# module_state.net
KiCad netlist of a schematic drawn in EAGLE
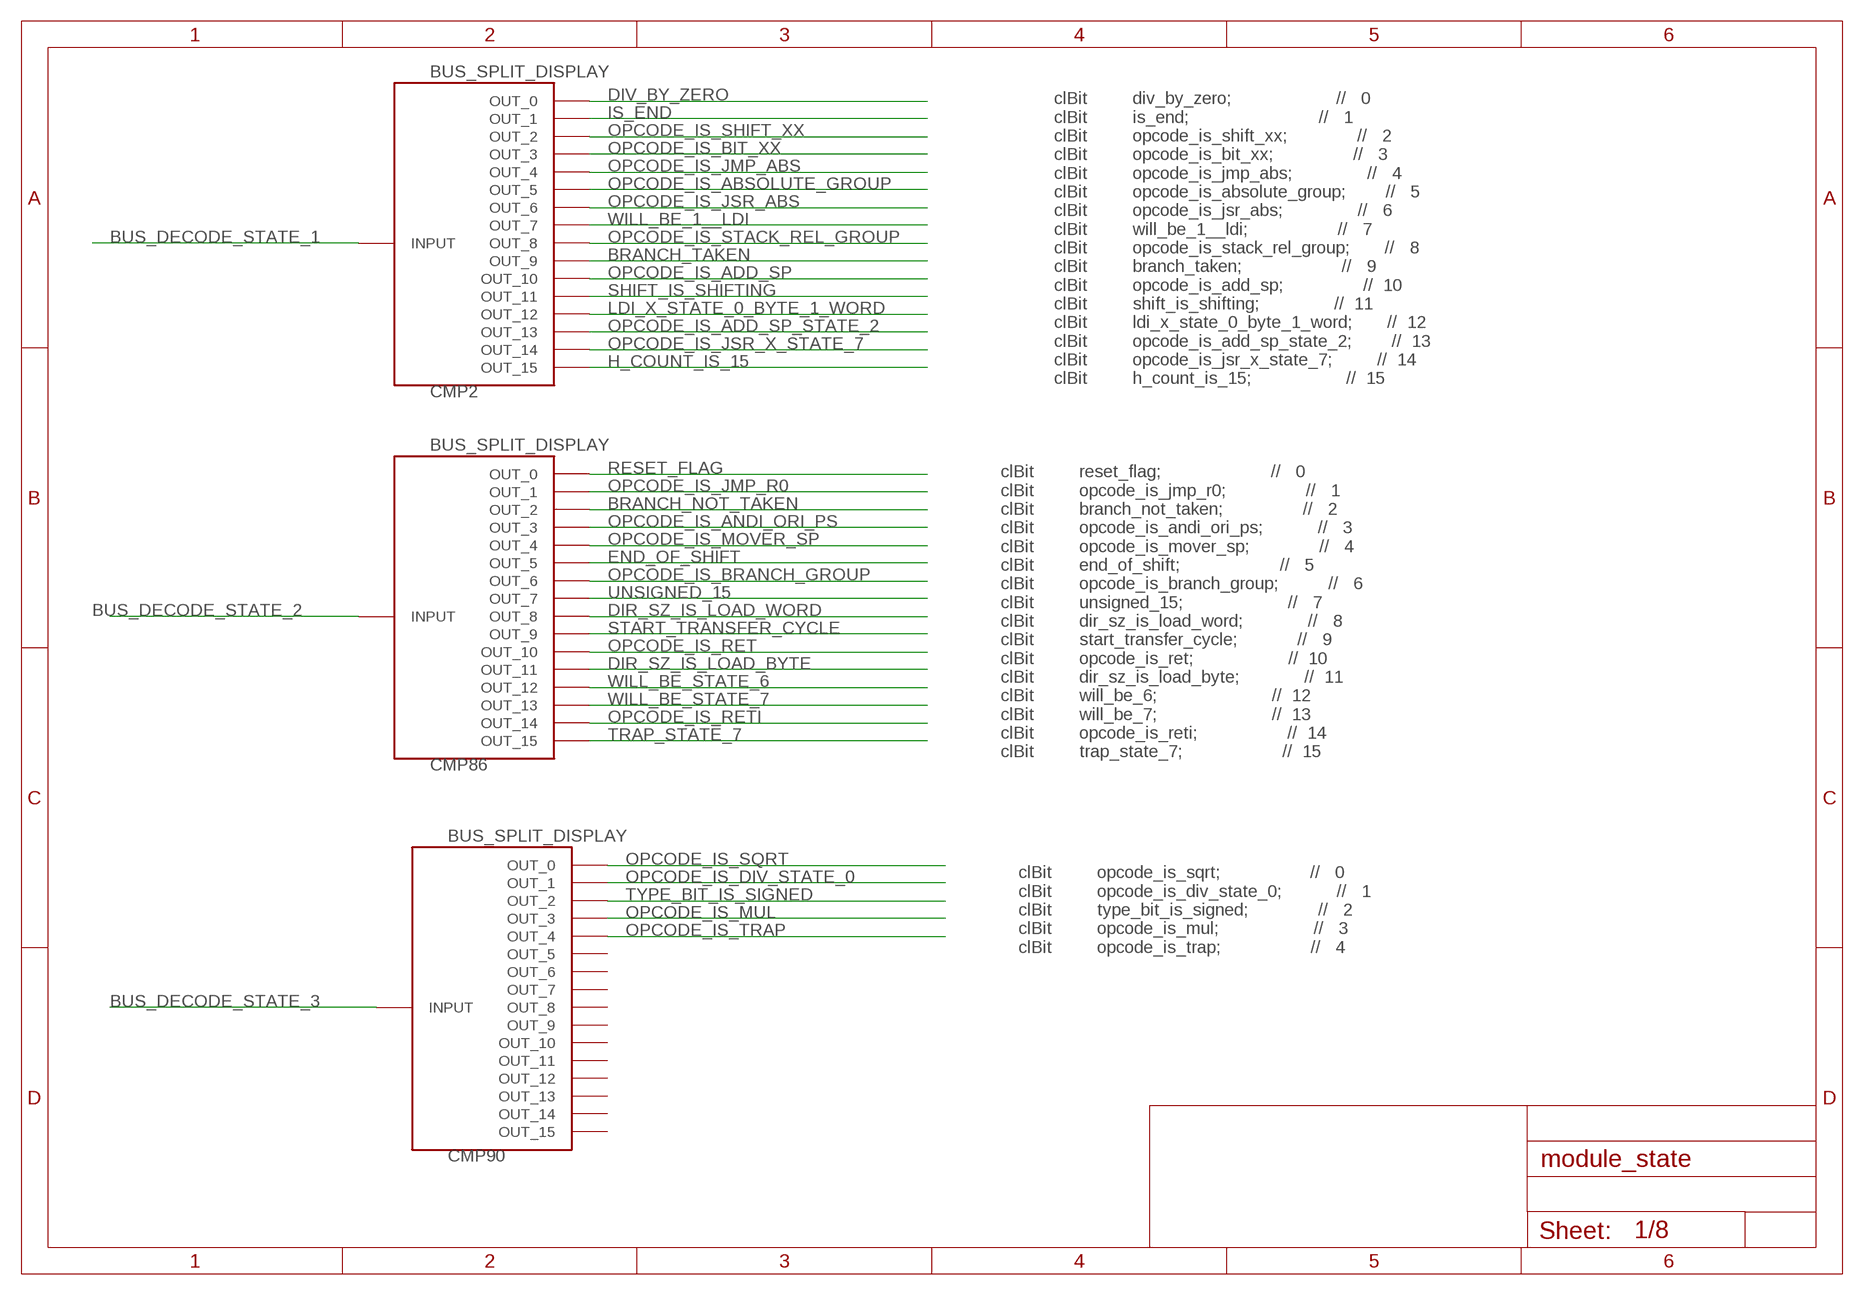
[diagram p0: schematic, sheet 1]
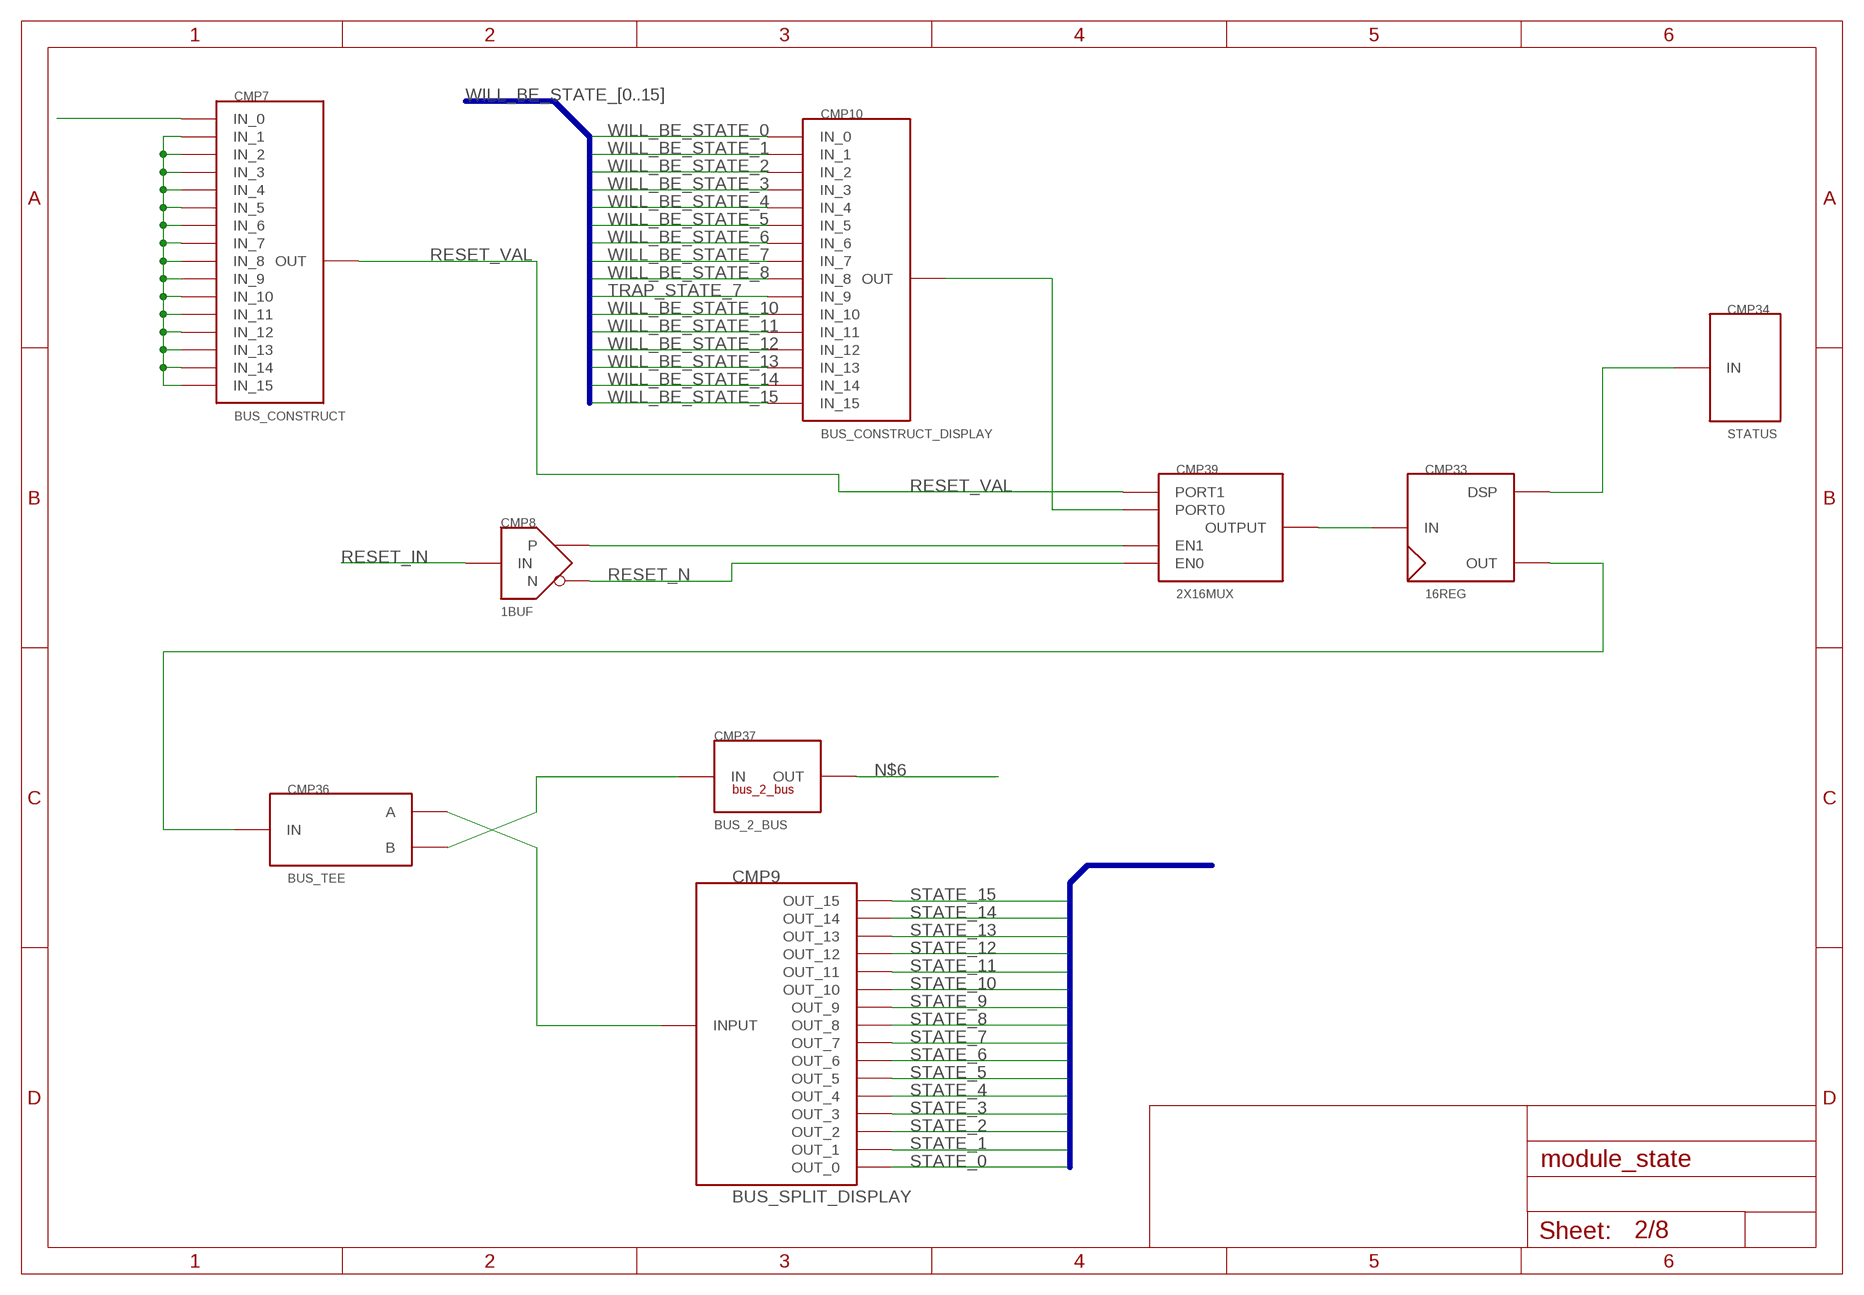
[diagram p1: schematic, sheet 2]
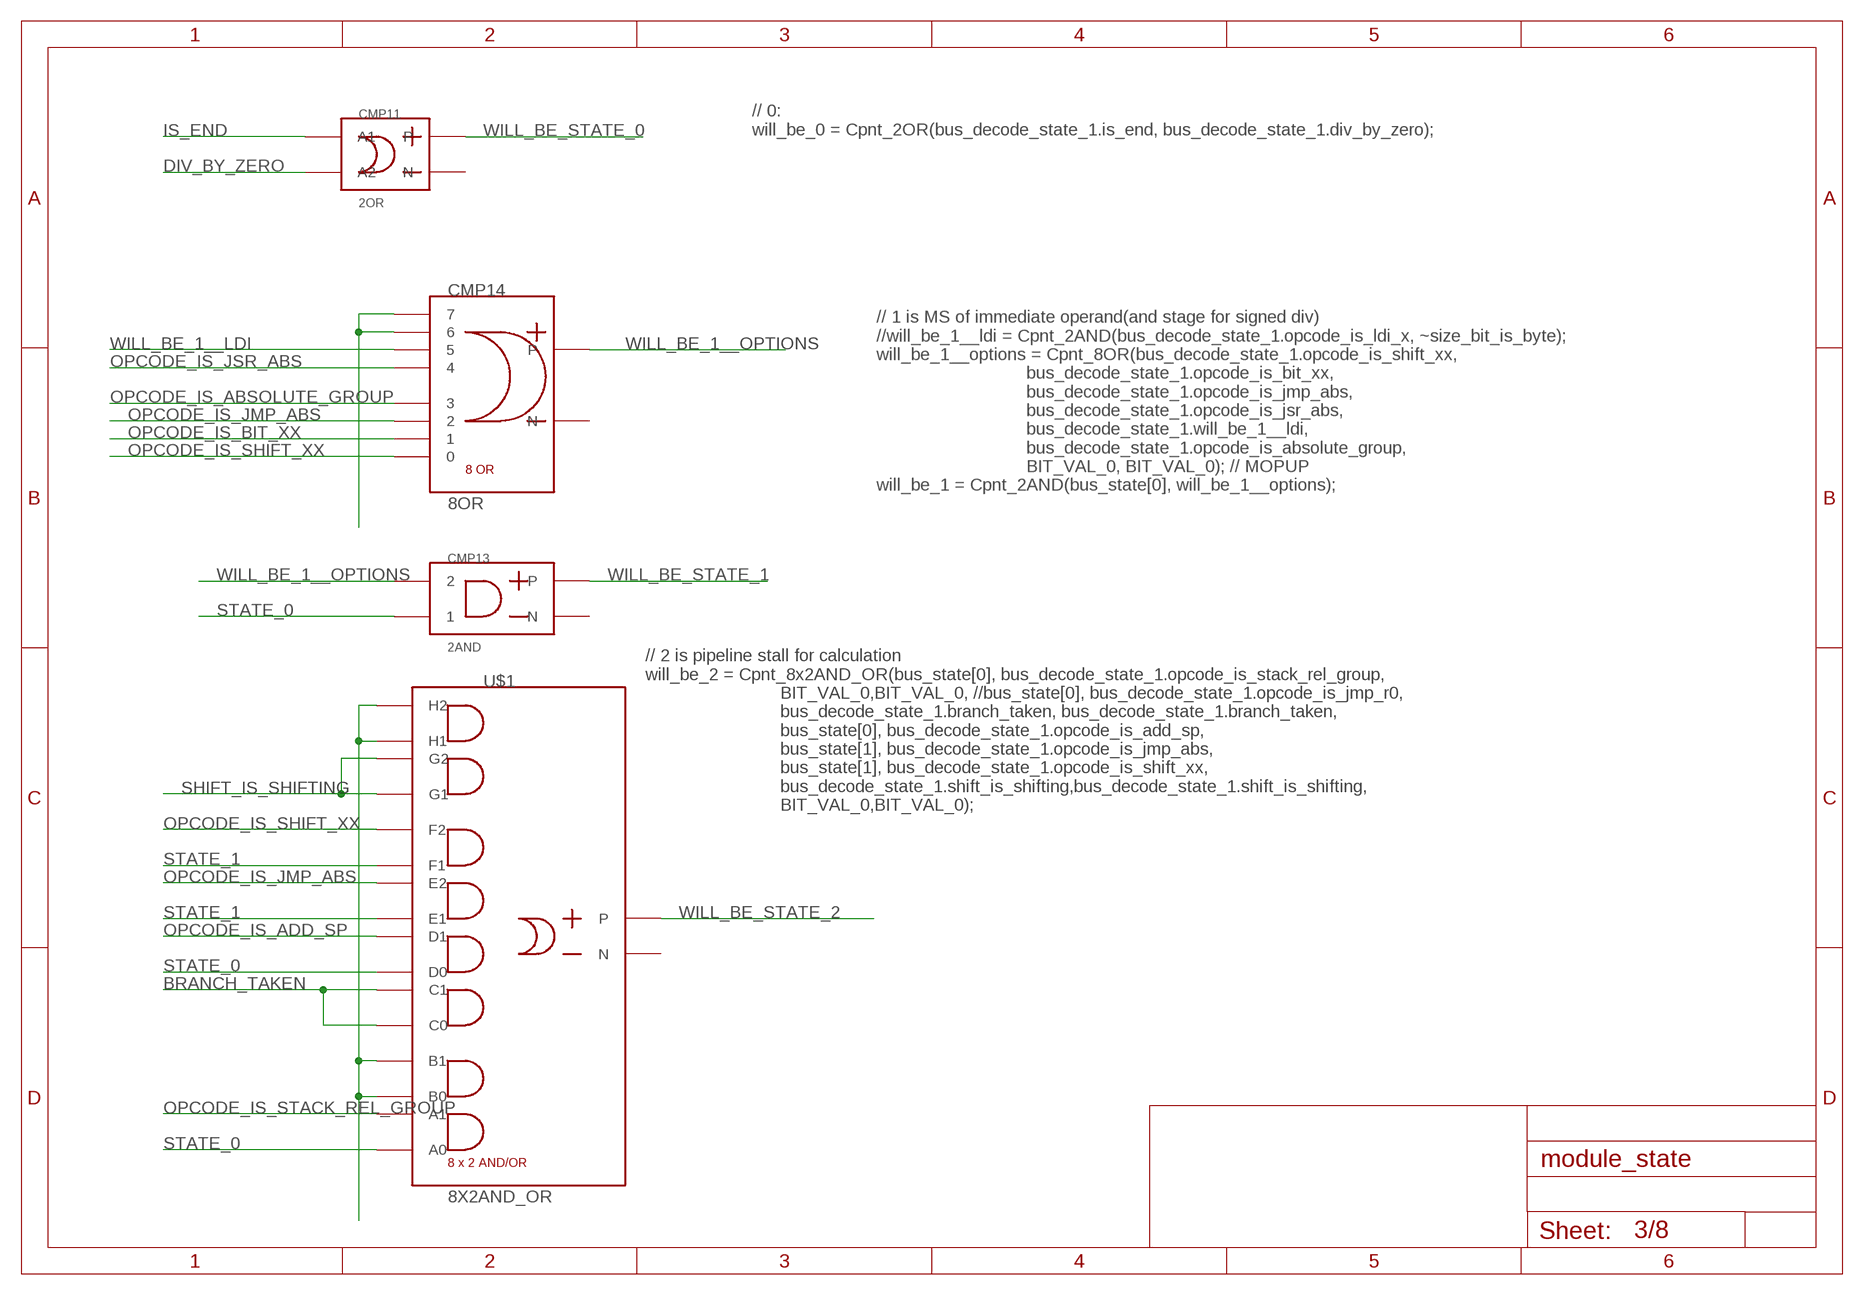
[diagram p2: schematic, sheet 3]
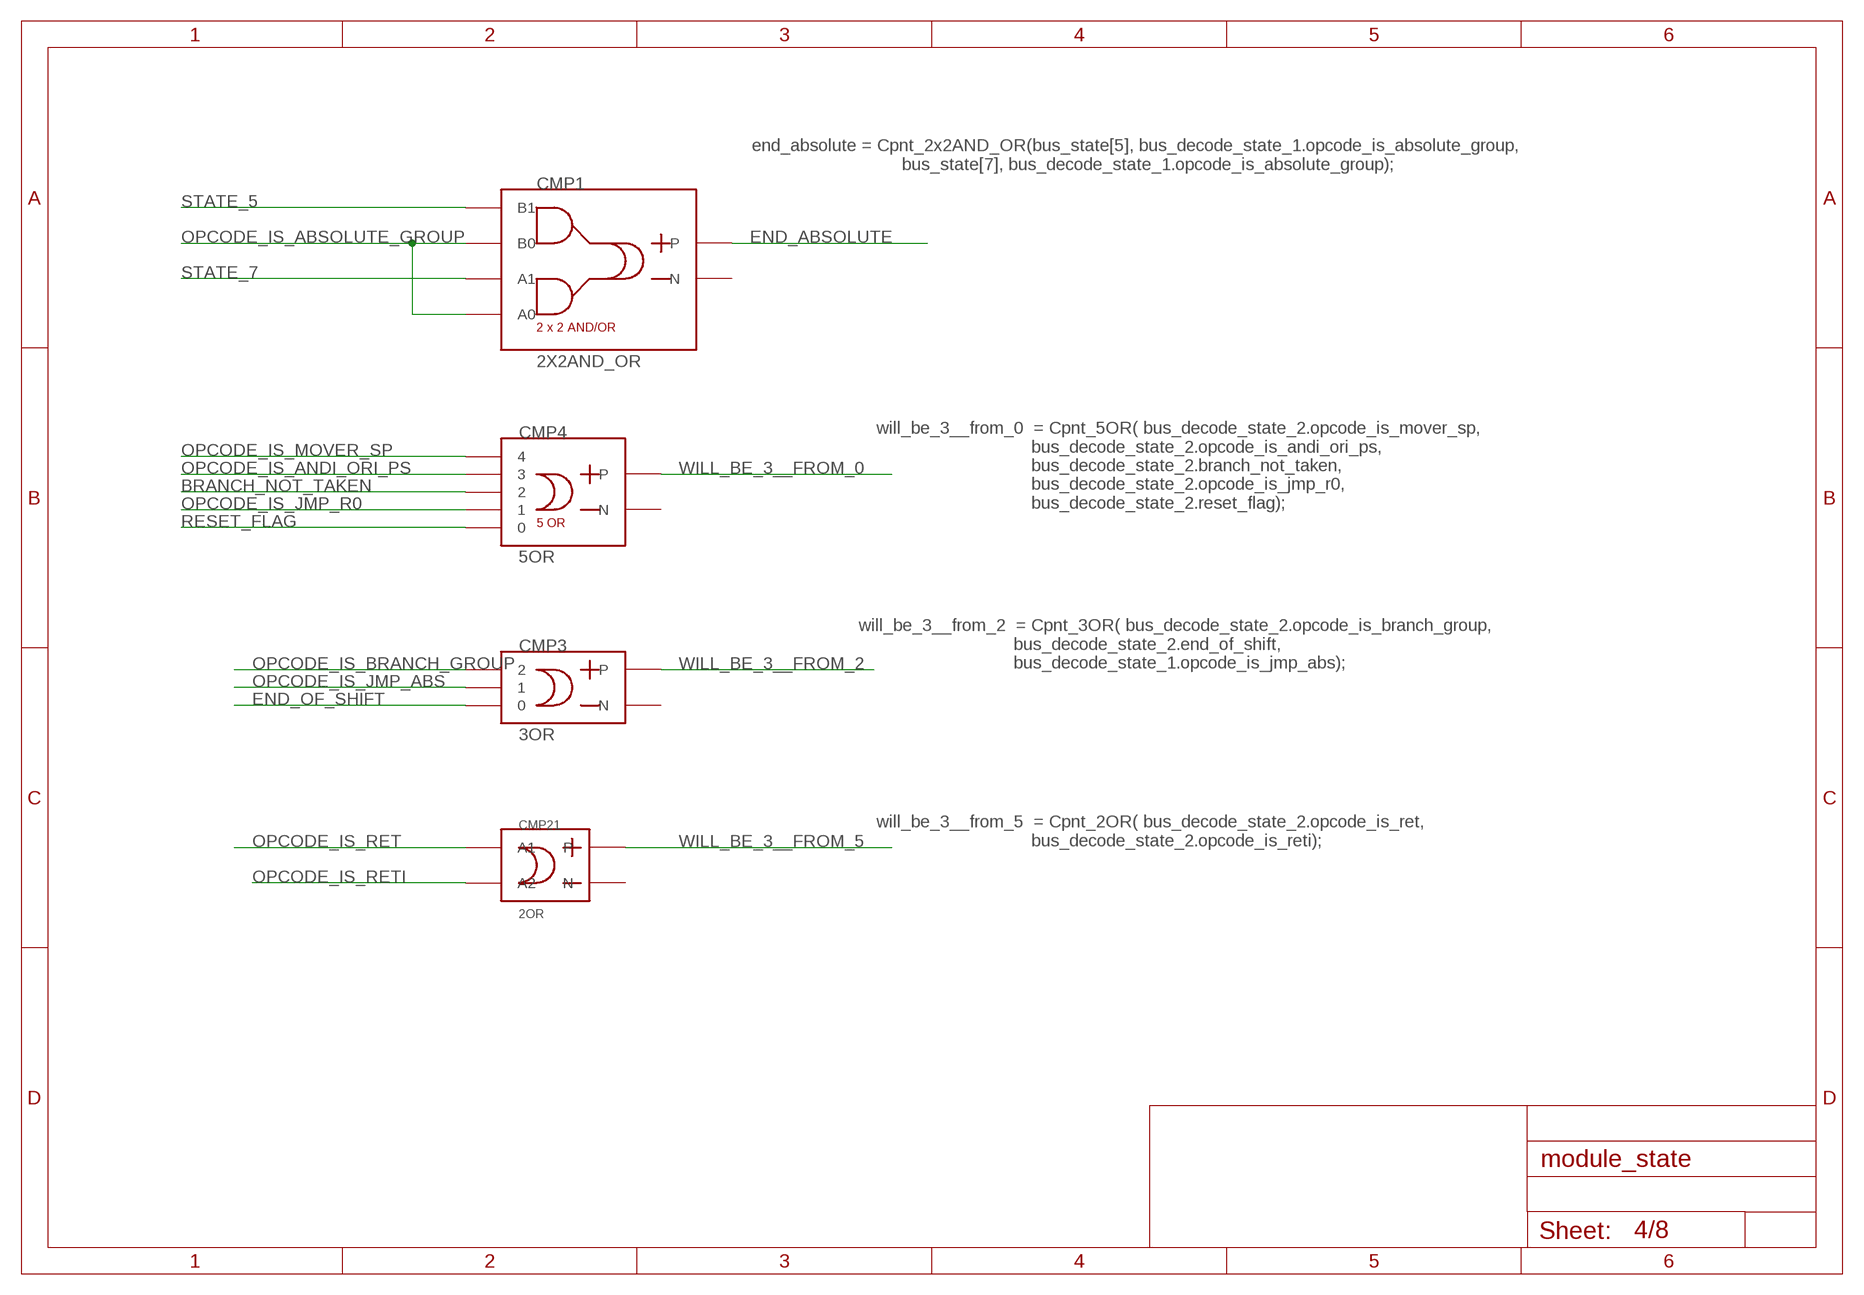
[diagram p3: schematic, sheet 4]
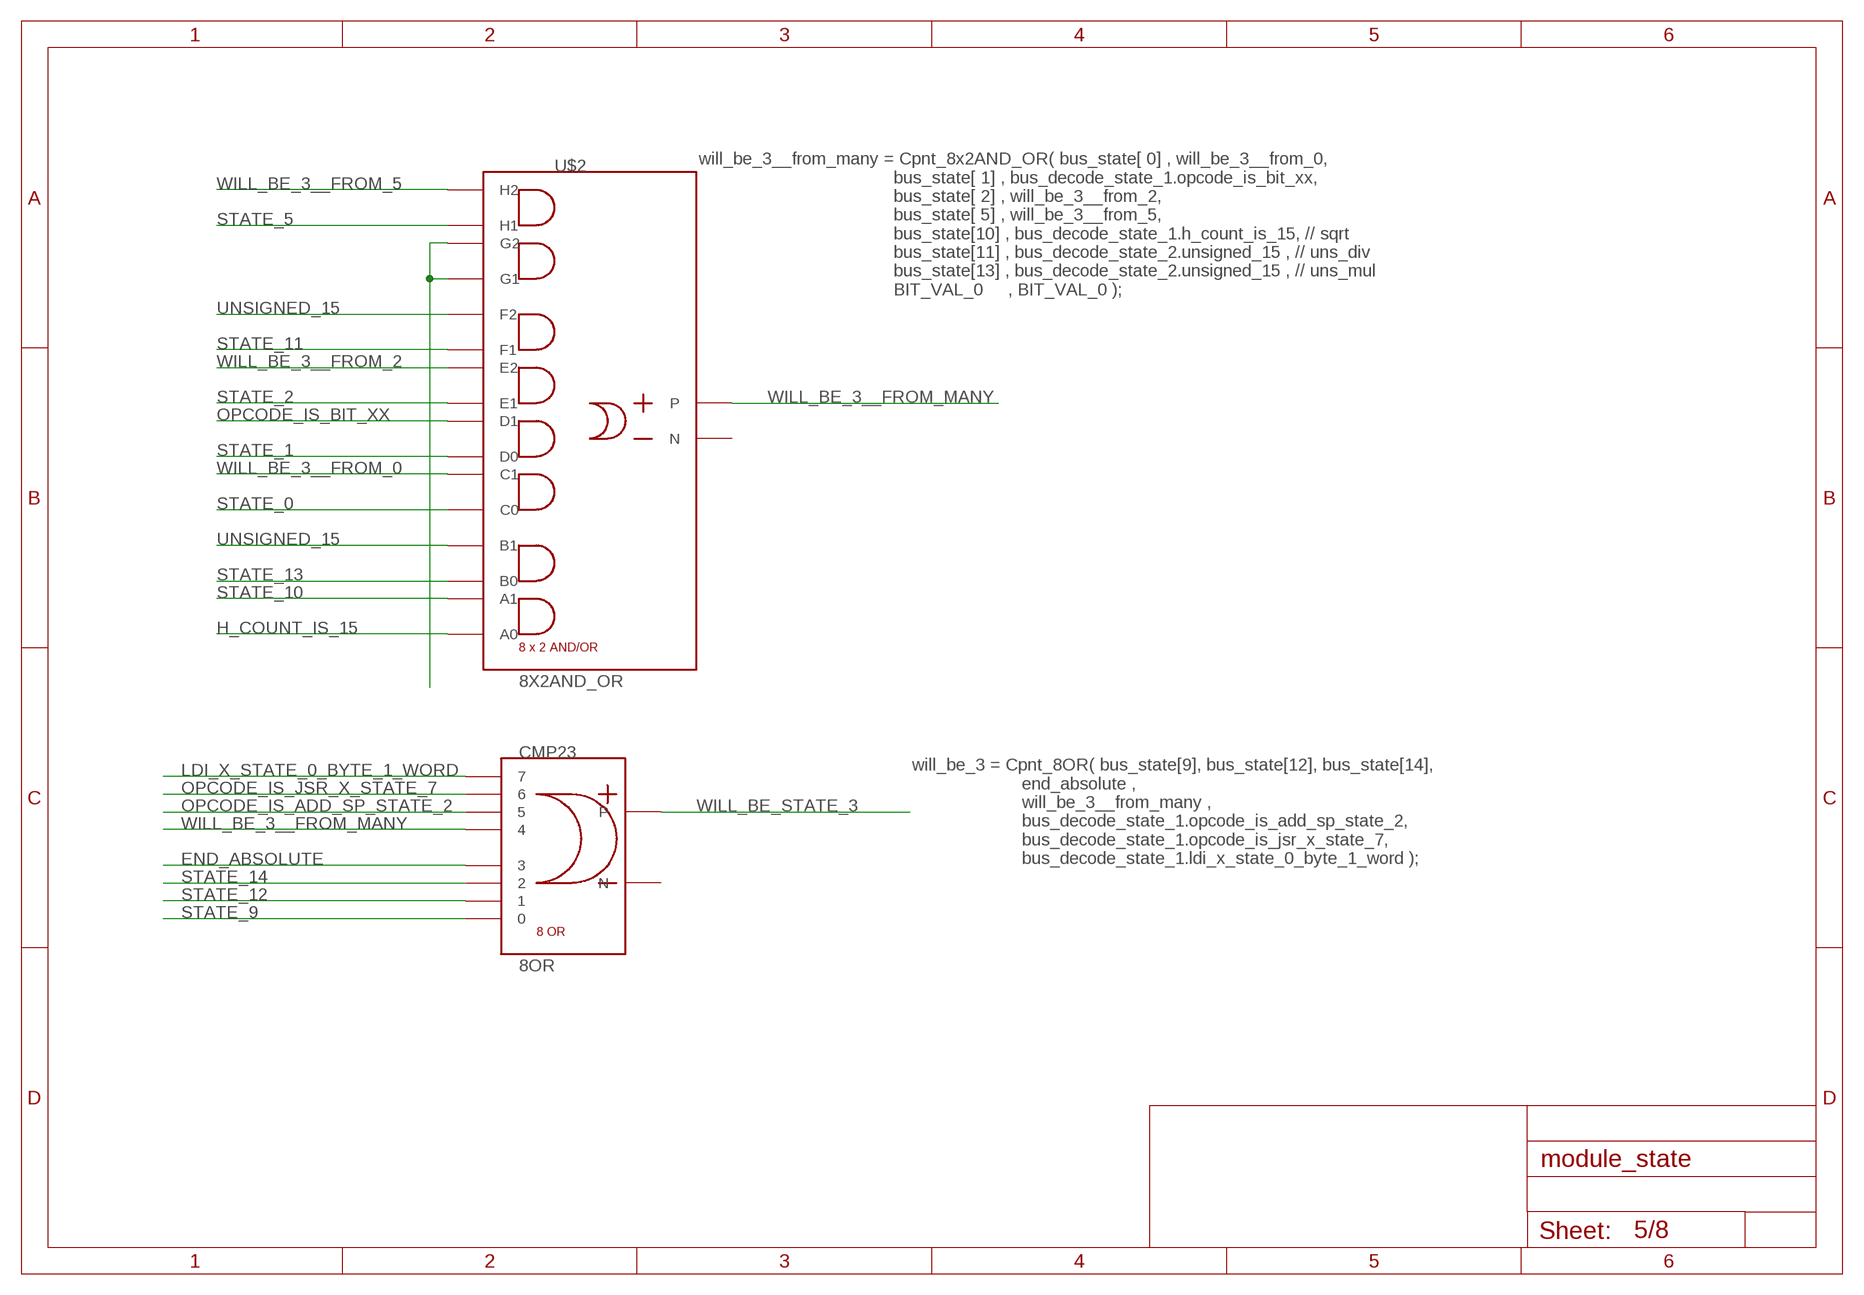
[diagram p4: schematic, sheet 5]
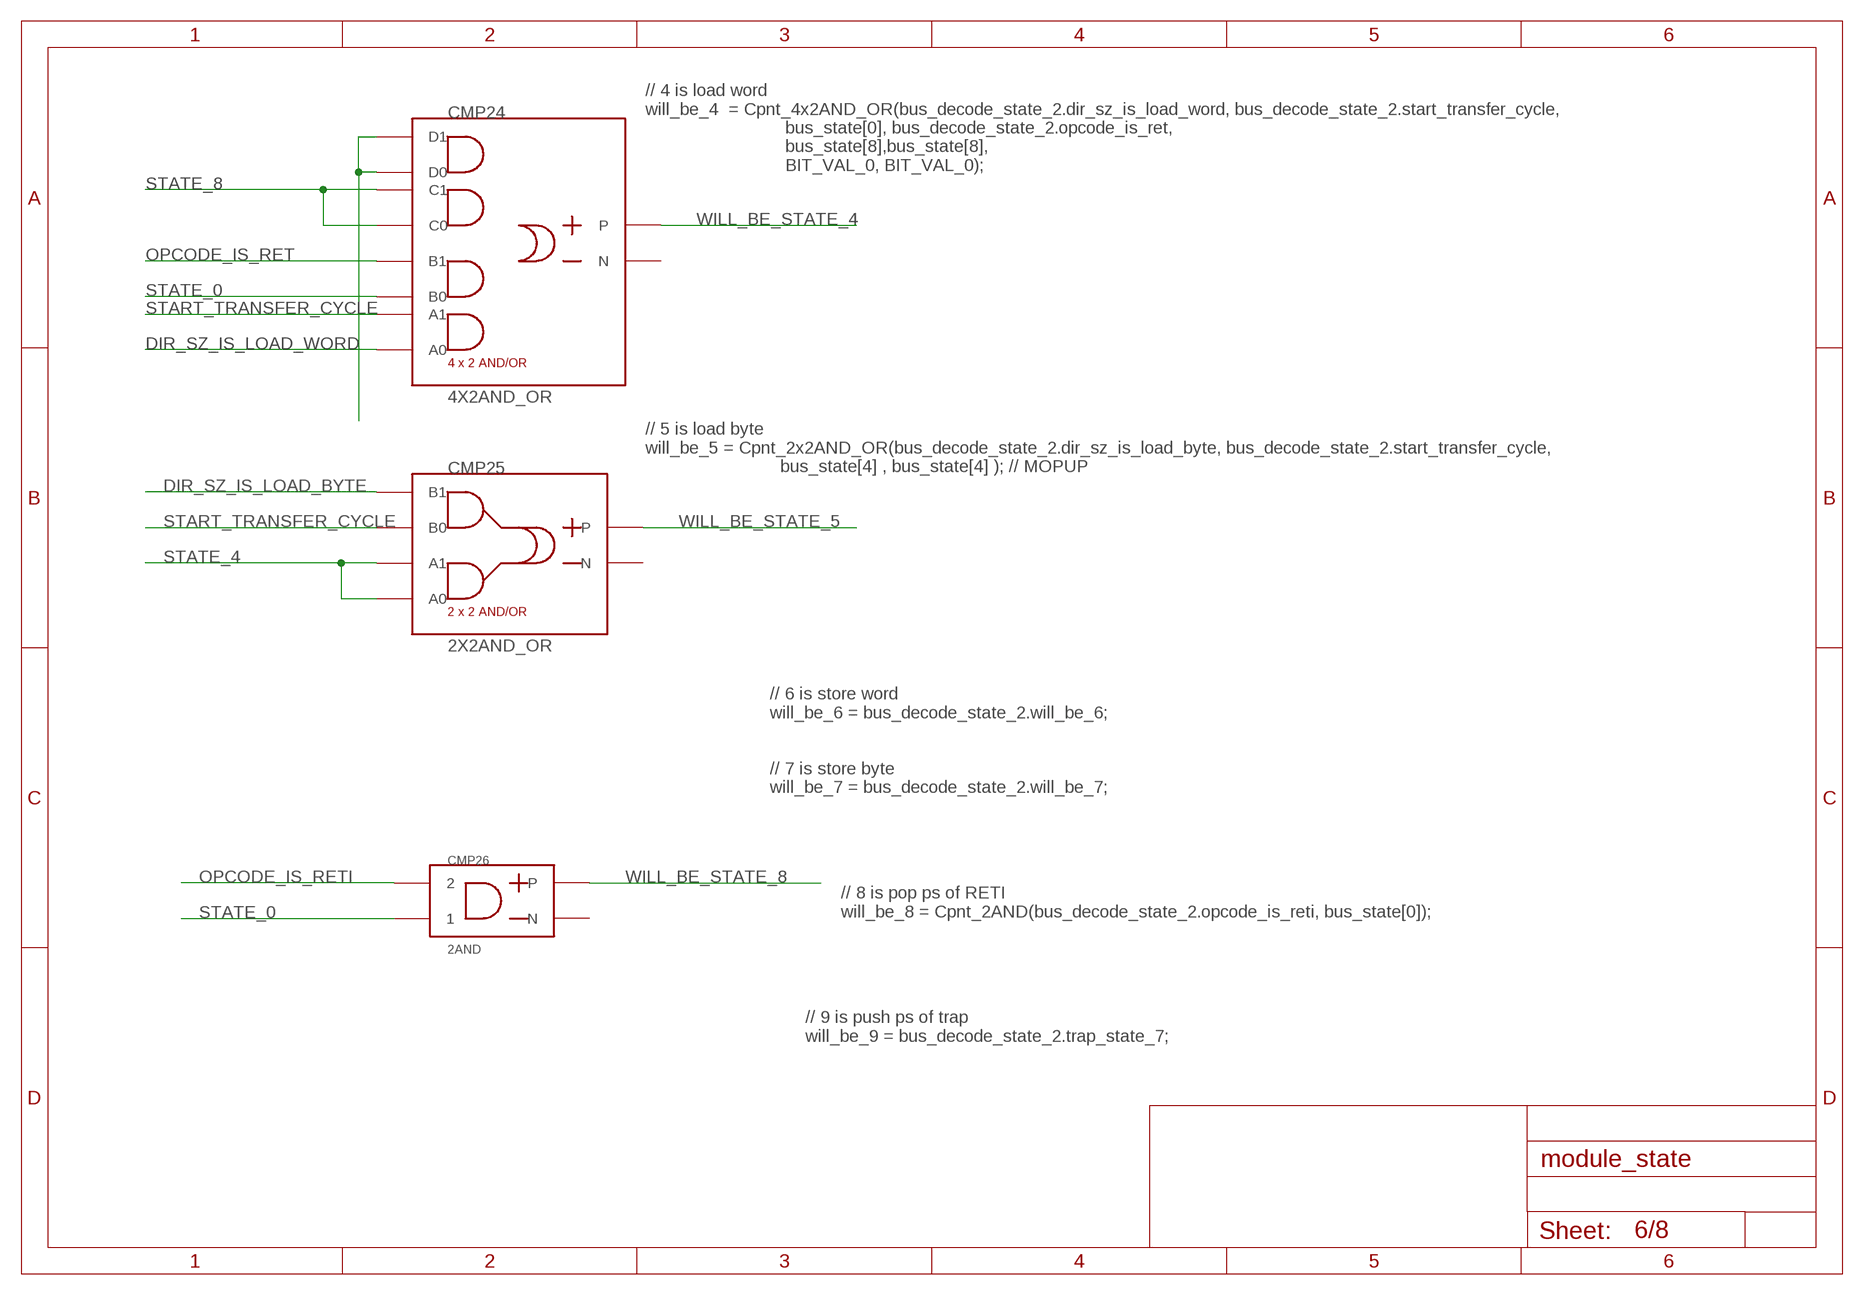
[diagram p5: schematic, sheet 6]
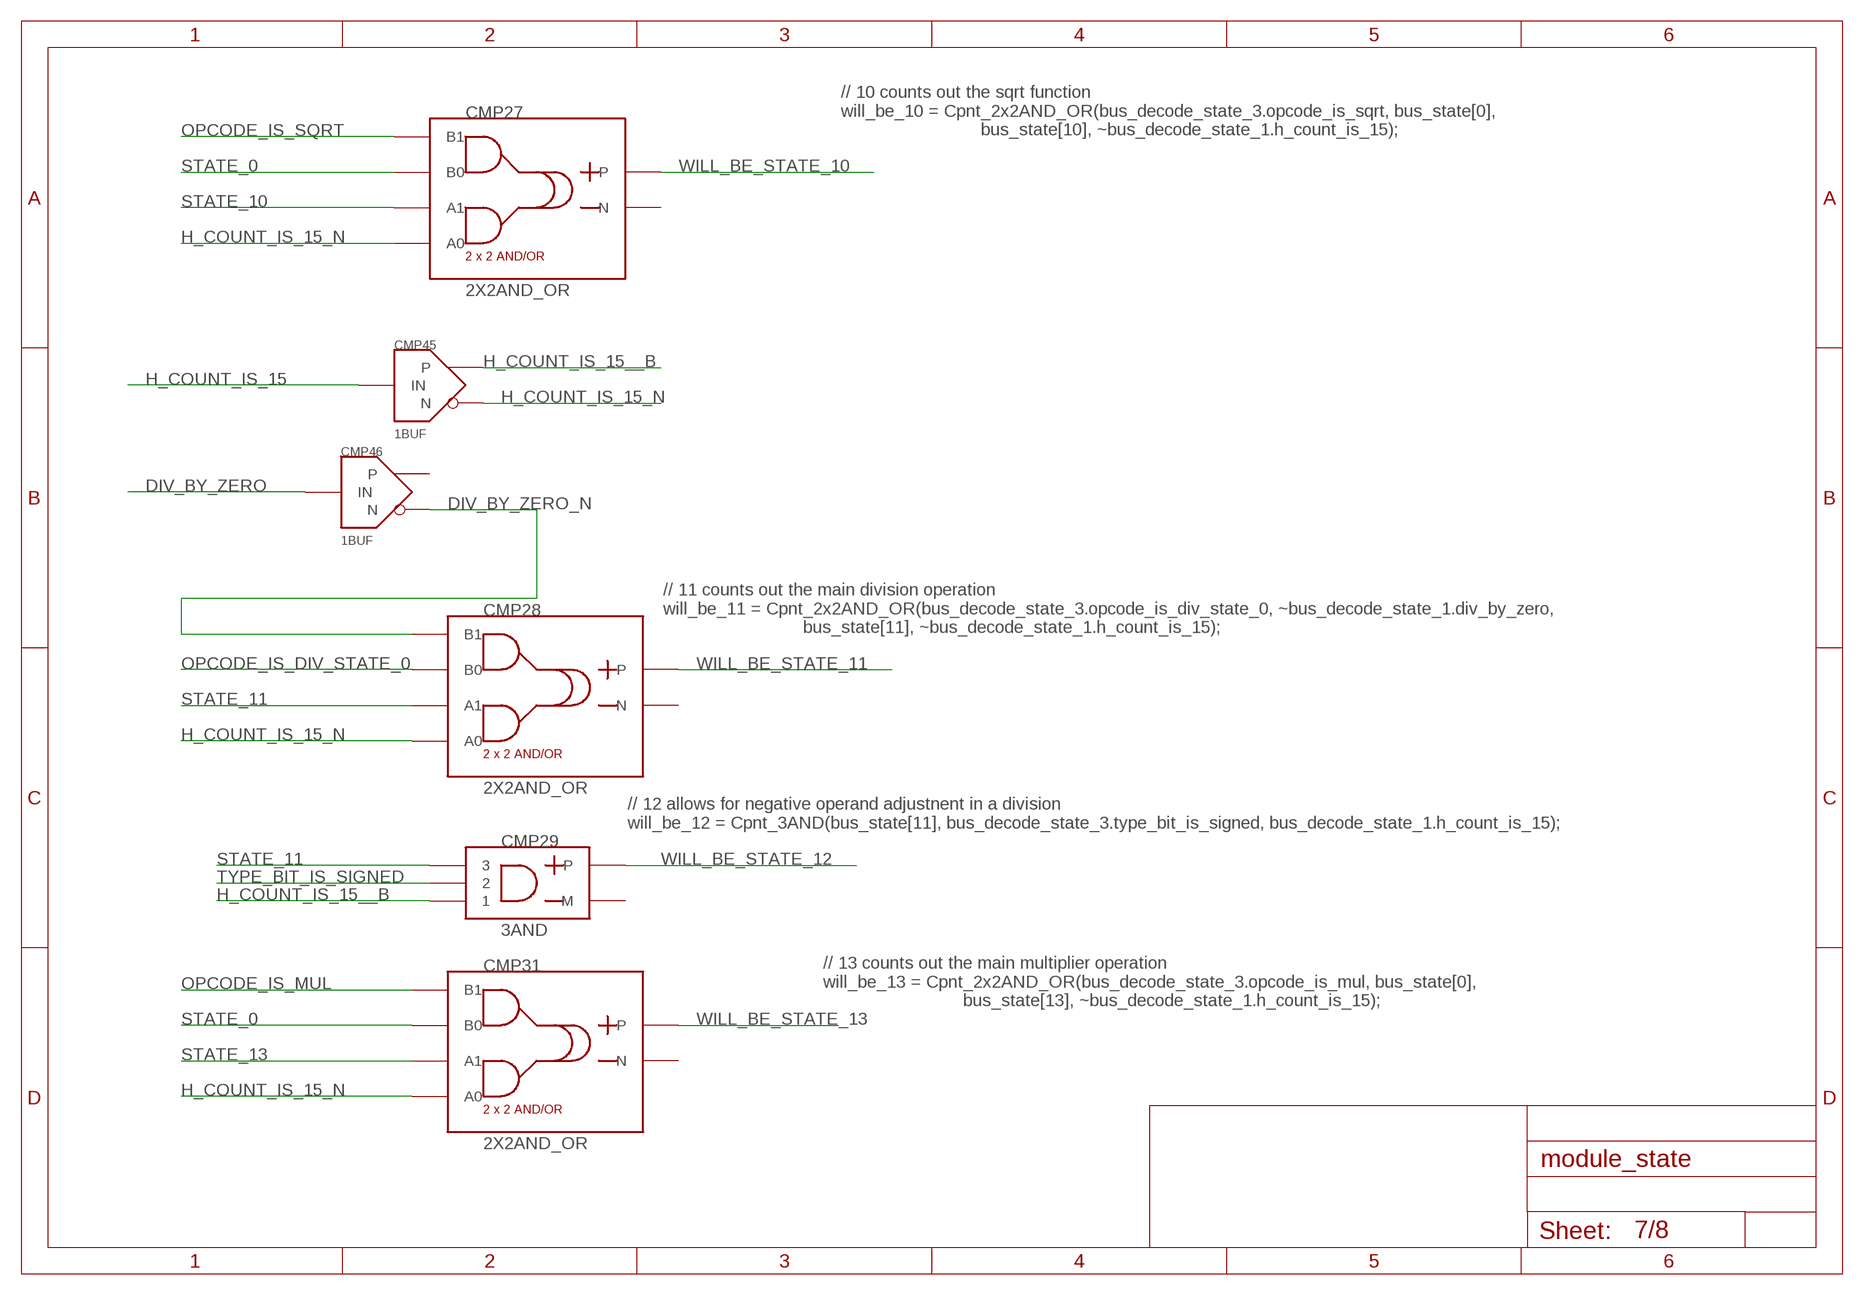
[diagram p6: schematic, sheet 7]
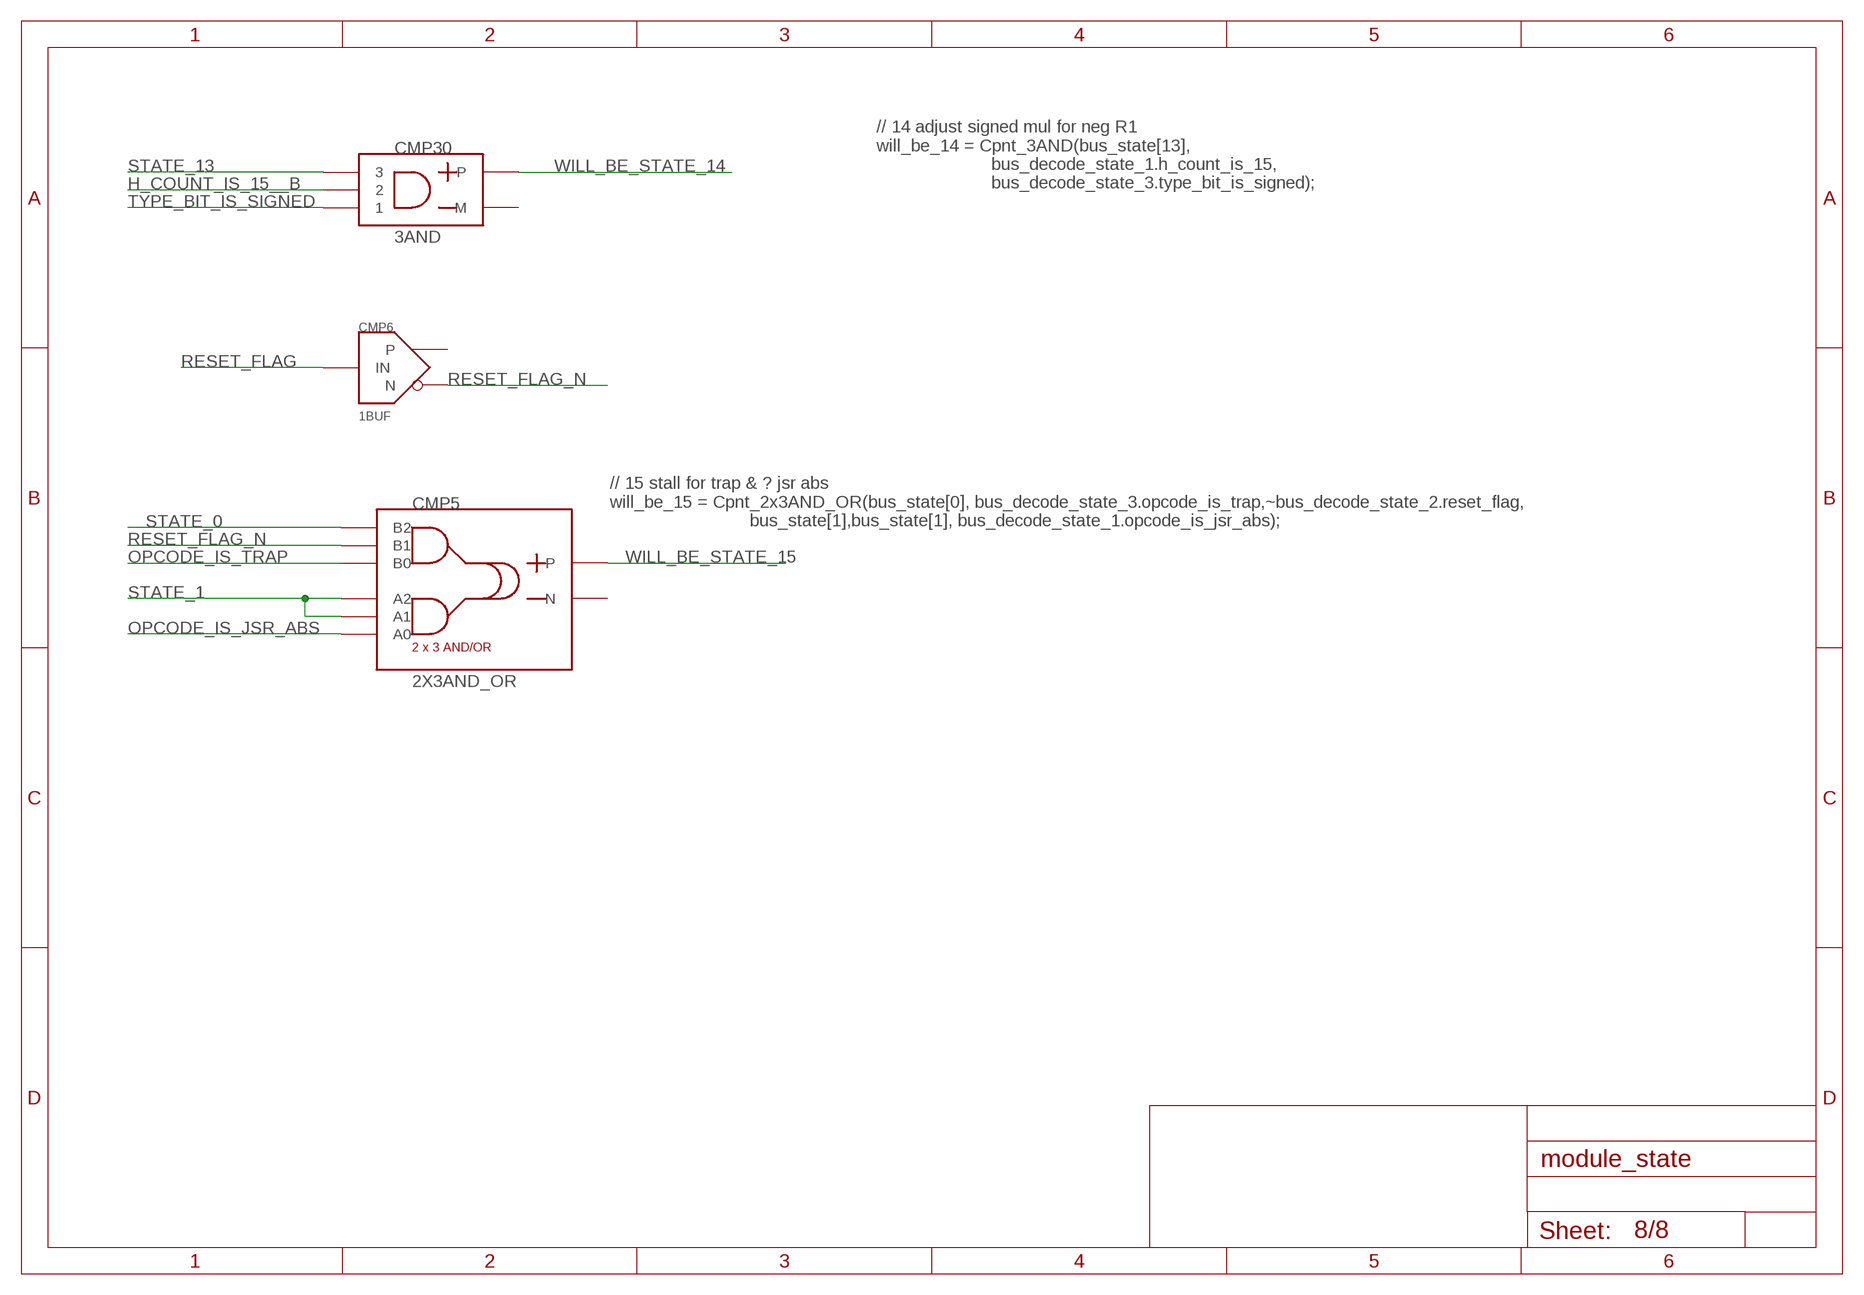
[diagram p7: schematic, sheet 8]

(export (version "E")
  (design (tool "Eeschema 10.0.6"))
  (components
    (comp (ref "CMP5")
      (value "2X3AND_OR")
      (footprint "eagle-import:2X3AND_OR")
      (libsource (lib "eagle-import") (part "2X3AND_OR"))
    )
    (comp (ref "CMP6")
      (value "1BUF")
      (footprint "eagle-import:1BUF")
      (libsource (lib "eagle-import") (part "1BUF"))
    )
    (comp (ref "CMP30")
      (value "3AND")
      (footprint "eagle-import:3AND")
      (libsource (lib "eagle-import") (part "3AND"))
    )
    (comp (ref "CMP7")
      (value "BUS_CONSTRUCT")
      (footprint "eagle-import:BUS_SPLIT")
      (libsource (lib "eagle-import") (part "BUS_CONSTRUCT"))
    )
    (comp (ref "CMP8")
      (value "1BUF")
      (footprint "eagle-import:1BUF")
      (libsource (lib "eagle-import") (part "1BUF"))
    )
    (comp (ref "CMP9")
      (value "BUS_SPLIT_DISPLAY")
      (footprint "eagle-import:BUS_SPLIT_DISPLAY")
      (libsource (lib "eagle-import") (part "BUS_SPLIT_DISPLAY"))
    )
    (comp (ref "CMP10")
      (value "BUS_CONSTRUCT_DISPLAY")
      (footprint "eagle-import:BUS_SPLIT_DISPLAY")
      (libsource (lib "eagle-import") (part "BUS_CONSTRUCT_DISPLAY"))
    )
    (comp (ref "CMP33")
      (value "16REG")
      (footprint "eagle-import:16REG")
      (libsource (lib "eagle-import") (part "16REG"))
    )
    (comp (ref "CMP34")
      (value "STATUS")
      (footprint "eagle-import:STATUS")
      (libsource (lib "eagle-import") (part "STATUS"))
    )
    (comp (ref "CMP36")
      (value "BUS_TEE")
      (footprint "eagle-import:BUS_TEE")
      (libsource (lib "eagle-import") (part "BUS_TEE"))
    )
    (comp (ref "CMP37")
      (value "BUS_2_BUS")
      (footprint "eagle-import:BUS2BUS")
      (libsource (lib "eagle-import") (part "BUS_2_BUS"))
    )
    (comp (ref "CMP39")
      (value "2X16MUX")
      (footprint "eagle-import:2X16MUX")
      (libsource (lib "eagle-import") (part "2X16MUX"))
    )
    (comp (ref "CMP1")
      (value "2X2AND_OR")
      (footprint "eagle-import:2X2AND_OR")
      (libsource (lib "eagle-import") (part "2X2AND_OR"))
    )
    (comp (ref "CMP3")
      (value "3OR")
      (footprint "eagle-import:3OR")
      (libsource (lib "eagle-import") (part "3OR"))
    )
    (comp (ref "CMP4")
      (value "5OR")
      (footprint "eagle-import:5OR")
      (libsource (lib "eagle-import") (part "5OR"))
    )
    (comp (ref "CMP21")
      (value "2OR")
      (footprint "eagle-import:2OR")
      (libsource (lib "eagle-import") (part "2OR"))
    )
    (comp (ref "CMP23")
      (value "8OR")
      (footprint "eagle-import:8OR")
      (libsource (lib "eagle-import") (part "8OR"))
    )
    (comp (ref "U$2")
      (value "8X2AND_OR")
      (footprint "eagle-import:8X2AND_OR")
      (libsource (lib "eagle-import") (part "8X2AND_OR"))
    )
    (comp (ref "CMP24")
      (value "4X2AND_OR")
      (footprint "eagle-import:4X2AND_OR")
      (libsource (lib "eagle-import") (part "4X2AND_OR"))
    )
    (comp (ref "CMP25")
      (value "2X2AND_OR")
      (footprint "eagle-import:2X2AND_OR")
      (libsource (lib "eagle-import") (part "2X2AND_OR"))
    )
    (comp (ref "CMP26")
      (value "2AND")
      (footprint "eagle-import:2AND")
      (libsource (lib "eagle-import") (part "2AND"))
    )
    (comp (ref "CMP2")
      (value "BUS_SPLIT_DISPLAY")
      (footprint "eagle-import:BUS_SPLIT_DISPLAY")
      (libsource (lib "eagle-import") (part "BUS_SPLIT_DISPLAY"))
    )
    (comp (ref "CMP86")
      (value "BUS_SPLIT_DISPLAY")
      (footprint "eagle-import:BUS_SPLIT_DISPLAY")
      (libsource (lib "eagle-import") (part "BUS_SPLIT_DISPLAY"))
    )
    (comp (ref "CMP90")
      (value "BUS_SPLIT_DISPLAY")
      (footprint "eagle-import:BUS_SPLIT_DISPLAY")
      (libsource (lib "eagle-import") (part "BUS_SPLIT_DISPLAY"))
    )
    (comp (ref "CMP27")
      (value "2X2AND_OR")
      (footprint "eagle-import:2X2AND_OR")
      (libsource (lib "eagle-import") (part "2X2AND_OR"))
    )
    (comp (ref "CMP28")
      (value "2X2AND_OR")
      (footprint "eagle-import:2X2AND_OR")
      (libsource (lib "eagle-import") (part "2X2AND_OR"))
    )
    (comp (ref "CMP29")
      (value "3AND")
      (footprint "eagle-import:3AND")
      (libsource (lib "eagle-import") (part "3AND"))
    )
    (comp (ref "CMP31")
      (value "2X2AND_OR")
      (footprint "eagle-import:2X2AND_OR")
      (libsource (lib "eagle-import") (part "2X2AND_OR"))
    )
    (comp (ref "CMP45")
      (value "1BUF")
      (footprint "eagle-import:1BUF")
      (libsource (lib "eagle-import") (part "1BUF"))
    )
    (comp (ref "CMP46")
      (value "1BUF")
      (footprint "eagle-import:1BUF")
      (libsource (lib "eagle-import") (part "1BUF"))
    )
    (comp (ref "CMP11")
      (value "2OR")
      (footprint "eagle-import:2OR")
      (libsource (lib "eagle-import") (part "2OR"))
    )
    (comp (ref "CMP13")
      (value "2AND")
      (footprint "eagle-import:2AND")
      (libsource (lib "eagle-import") (part "2AND"))
    )
    (comp (ref "CMP14")
      (value "8OR")
      (footprint "eagle-import:8OR")
      (libsource (lib "eagle-import") (part "8OR"))
    )
    (comp (ref "U$1")
      (value "8X2AND_OR")
      (footprint "eagle-import:8X2AND_OR")
      (libsource (lib "eagle-import") (part "8X2AND_OR"))
    )
  )
  (nets
    (net (code "3") (name "BRANCH_NOT_TAKEN") (class "Default")
      (node (ref "CMP4") (pin "3") (pinfunction "2_3") (pintype "input"))
      (node (ref "CMP86") (pin "P$3") (pinfunction "OUT_2_P$3") (pintype "output"))
    )
    (net (code "4") (name "BRANCH_TAKEN") (class "Default")
      (node (ref "CMP2") (pin "P$10") (pinfunction "OUT_9_P$10") (pintype "output"))
      (node (ref "U$1") (pin "P$5") (pinfunction "C0_P$5") (pintype "input"))
      (node (ref "U$1") (pin "P$6") (pinfunction "C1_P$6") (pintype "input"))
    )
    (net (code "5") (name "BUS_DECODE_STATE_1") (class "Default")
      (node (ref "CMP2") (pin "INPUT") (pinfunction "INPUT_INPUT") (pintype "input"))
    )
    (net (code "6") (name "BUS_DECODE_STATE_2") (class "Default")
      (node (ref "CMP86") (pin "INPUT") (pinfunction "INPUT_INPUT") (pintype "input"))
    )
    (net (code "7") (name "BUS_DECODE_STATE_3") (class "Default")
      (node (ref "CMP90") (pin "INPUT") (pinfunction "INPUT_INPUT") (pintype "input"))
    )
    (net (code "8") (name "DIR_SZ_IS_LOAD_BYTE") (class "Default")
      (node (ref "CMP25") (pin "P$4") (pinfunction "B1_P$4") (pintype "input"))
      (node (ref "CMP86") (pin "P$12") (pinfunction "OUT_11_P$12") (pintype "output"))
    )
    (net (code "9") (name "DIR_SZ_IS_LOAD_WORD") (class "Default")
      (node (ref "CMP24") (pin "P$1") (pinfunction "A0_P$1") (pintype "input"))
      (node (ref "CMP86") (pin "P$9") (pinfunction "OUT_8_P$9") (pintype "output"))
    )
    (net (code "10") (name "DIV_BY_ZERO") (class "Default")
      (node (ref "CMP11") (pin "P$1") (pinfunction "A2_P$1") (pintype "input"))
      (node (ref "CMP2") (pin "P$1") (pinfunction "OUT_0_P$1") (pintype "output"))
      (node (ref "CMP46") (pin "IN") (pinfunction "IN_IN") (pintype "input"))
    )
    (net (code "11") (name "DIV_BY_ZERO_N") (class "Default")
      (node (ref "CMP28") (pin "P$4") (pinfunction "B1_P$4") (pintype "input"))
      (node (ref "CMP46") (pin "N") (pinfunction "N_N") (pintype "output"))
    )
    (net (code "12") (name "END_ABSOLUTE") (class "Default")
      (node (ref "CMP1") (pin "OUT_P") (pinfunction "P_OUT_P") (pintype "output"))
      (node (ref "CMP23") (pin "8") (pinfunction "7_8") (pintype "input"))
    )
    (net (code "13") (name "END_OF_SHIFT") (class "Default")
      (node (ref "CMP3") (pin "P$1") (pinfunction "0_P$1") (pintype "input"))
      (node (ref "CMP86") (pin "P$6") (pinfunction "OUT_5_P$6") (pintype "output"))
    )
    (net (code "14") (name "H_COUNT_IS_15") (class "Default")
      (node (ref "CMP2") (pin "P$16") (pinfunction "OUT_15_P$16") (pintype "output"))
      (node (ref "CMP45") (pin "IN") (pinfunction "IN_IN") (pintype "input"))
      (node (ref "U$2") (pin "P$1") (pinfunction "A0_P$1") (pintype "input"))
    )
    (net (code "15") (name "H_COUNT_IS_15_N") (class "Default")
      (node (ref "CMP27") (pin "P$1") (pinfunction "A0_P$1") (pintype "input"))
      (node (ref "CMP28") (pin "P$1") (pinfunction "A0_P$1") (pintype "input"))
      (node (ref "CMP31") (pin "P$1") (pinfunction "A0_P$1") (pintype "input"))
      (node (ref "CMP45") (pin "N") (pinfunction "N_N") (pintype "output"))
    )
    (net (code "16") (name "H_COUNT_IS_15__B") (class "Default")
      (node (ref "CMP29") (pin "P$1") (pinfunction "1_P$1") (pintype "input"))
      (node (ref "CMP30") (pin "P$2") (pinfunction "2_P$2") (pintype "input"))
      (node (ref "CMP45") (pin "P") (pinfunction "P_P") (pintype "output"))
    )
    (net (code "17") (name "IS_END") (class "Default")
      (node (ref "CMP11") (pin "P$2") (pinfunction "A1_P$2") (pintype "input"))
      (node (ref "CMP2") (pin "P$2") (pinfunction "OUT_1_P$2") (pintype "output"))
    )
    (net (code "18") (name "LDI_X_STATE_0_BYTE_1_WORD") (class "Default")
      (node (ref "CMP2") (pin "P$13") (pinfunction "OUT_12_P$13") (pintype "output"))
      (node (ref "CMP23") (pin "4") (pinfunction "3_4") (pintype "input"))
    )
    (net (code "19") (name "N$6") (class "Default")
      (node (ref "CMP37") (pin "P$2") (pinfunction "OUT_P$2") (pintype "output"))
    )
    (net (code "20") (name "Net-(CMP7-IN_1)") (class "Default")
      (node (ref "CMP7") (pin "P$10") (pinfunction "IN_9_P$10") (pintype "input"))
      (node (ref "CMP7") (pin "P$11") (pinfunction "IN_10_P$11") (pintype "input"))
      (node (ref "CMP7") (pin "P$12") (pinfunction "IN_11_P$12") (pintype "input"))
      (node (ref "CMP7") (pin "P$13") (pinfunction "IN_12_P$13") (pintype "input"))
      (node (ref "CMP7") (pin "P$14") (pinfunction "IN_13_P$14") (pintype "input"))
      (node (ref "CMP7") (pin "P$15") (pinfunction "IN_14_P$15") (pintype "input"))
      (node (ref "CMP7") (pin "P$16") (pinfunction "IN_15_P$16") (pintype "input"))
      (node (ref "CMP7") (pin "P$2") (pinfunction "IN_1_P$2") (pintype "input"))
      (node (ref "CMP7") (pin "P$3") (pinfunction "IN_2_P$3") (pintype "input"))
      (node (ref "CMP7") (pin "P$4") (pinfunction "IN_3_P$4") (pintype "input"))
      (node (ref "CMP7") (pin "P$5") (pinfunction "IN_4_P$5") (pintype "input"))
      (node (ref "CMP7") (pin "P$6") (pinfunction "IN_5_P$6") (pintype "input"))
      (node (ref "CMP7") (pin "P$7") (pinfunction "IN_6_P$7") (pintype "input"))
      (node (ref "CMP7") (pin "P$8") (pinfunction "IN_7_P$8") (pintype "input"))
      (node (ref "CMP7") (pin "P$9") (pinfunction "IN_8_P$9") (pintype "input"))
    )
    (net (code "21") (name "Net-(CMP10-OUT)") (class "Default")
      (node (ref "CMP10") (pin "INPUT") (pinfunction "OUT_INPUT") (pintype "output"))
      (node (ref "CMP39") (pin "PORT0") (pinfunction "PORT0_PORT0") (pintype "input"))
    )
    (net (code "22") (name "Net-(CMP14-6)") (class "Default")
      (node (ref "CMP14") (pin "7") (pinfunction "6_7") (pintype "input"))
      (node (ref "CMP14") (pin "8") (pinfunction "7_8") (pintype "input"))
    )
    (net (code "23") (name "Net-(CMP24-D0)") (class "Default")
      (node (ref "CMP24") (pin "P$7") (pinfunction "D0_P$7") (pintype "input"))
      (node (ref "CMP24") (pin "P$8") (pinfunction "D1_P$8") (pintype "input"))
    )
    (net (code "24") (name "Net-(CMP33-DSP)") (class "Default")
      (node (ref "CMP33") (pin "DISPLAY") (pinfunction "DSP_DISPLAY") (pintype "output"))
      (node (ref "CMP34") (pin "P$1") (pinfunction "IN_P$1") (pintype "input"))
    )
    (net (code "25") (name "Net-(CMP33-IN)") (class "Default")
      (node (ref "CMP33") (pin "INPUT") (pinfunction "IN_INPUT") (pintype "input"))
      (node (ref "CMP39") (pin "OUT") (pinfunction "OUTPUT_OUT") (pintype "output"))
    )
    (net (code "26") (name "Net-(CMP36-A)") (class "Default")
      (node (ref "CMP36") (pin "OUT_A") (pinfunction "A_OUT_A") (pintype "output"))
      (node (ref "CMP9") (pin "INPUT") (pinfunction "INPUT_INPUT") (pintype "input"))
    )
    (net (code "27") (name "Net-(CMP36-B)") (class "Default")
      (node (ref "CMP36") (pin "OUTB") (pinfunction "B_OUTB") (pintype "output"))
      (node (ref "CMP37") (pin "P$1") (pinfunction "IN_P$1") (pintype "input"))
    )
    (net (code "28") (name "Net-(CMP36-IN)") (class "Default")
      (node (ref "CMP33") (pin "OUT") (pinfunction "OUT_OUT") (pintype "output"))
      (node (ref "CMP36") (pin "INPUT") (pinfunction "IN_INPUT") (pintype "input"))
    )
    (net (code "29") (name "Net-(CMP39-PadEN1)") (class "Default")
      (node (ref "CMP39") (pin "EN1") (pinfunction "EN1_EN1") (pintype "input"))
      (node (ref "CMP8") (pin "P") (pinfunction "P_P") (pintype "output"))
    )
    (net (code "30") (name "Net-(U$1-B0)") (class "Default")
      (node (ref "U$1") (pin "P$15") (pinfunction "H1_P$15") (pintype "input"))
      (node (ref "U$1") (pin "P$16") (pinfunction "H2_P$16") (pintype "input"))
      (node (ref "U$1") (pin "P$3") (pinfunction "B0_P$3") (pintype "input"))
      (node (ref "U$1") (pin "P$4") (pinfunction "B1_P$4") (pintype "input"))
    )
    (net (code "31") (name "Net-(U$2-G1)") (class "Default")
      (node (ref "U$2") (pin "P$13") (pinfunction "G1_P$13") (pintype "input"))
      (node (ref "U$2") (pin "P$14") (pinfunction "G2_P$14") (pintype "input"))
    )
    (net (code "32") (name "OPCODE_IS_ABSOLUTE_GROUP") (class "Default")
      (node (ref "CMP1") (pin "P$1") (pinfunction "A0_P$1") (pintype "input"))
      (node (ref "CMP1") (pin "P$3") (pinfunction "B0_P$3") (pintype "input"))
      (node (ref "CMP14") (pin "4") (pinfunction "3_4") (pintype "input"))
      (node (ref "CMP2") (pin "P$6") (pinfunction "OUT_5_P$6") (pintype "output"))
    )
    (net (code "33") (name "OPCODE_IS_ADD_SP") (class "Default")
      (node (ref "CMP2") (pin "P$11") (pinfunction "OUT_10_P$11") (pintype "output"))
      (node (ref "U$1") (pin "P$8") (pinfunction "D1_P$8") (pintype "input"))
    )
    (net (code "34") (name "OPCODE_IS_ADD_SP_STATE_2") (class "Default")
      (node (ref "CMP2") (pin "P$14") (pinfunction "OUT_13_P$14") (pintype "output"))
      (node (ref "CMP23") (pin "5") (pinfunction "4_5") (pintype "input"))
    )
    (net (code "35") (name "OPCODE_IS_ANDI_ORI_PS") (class "Default")
      (node (ref "CMP4") (pin "4") (pinfunction "3_4") (pintype "input"))
      (node (ref "CMP86") (pin "P$4") (pinfunction "OUT_3_P$4") (pintype "output"))
    )
    (net (code "36") (name "OPCODE_IS_BIT_XX") (class "Default")
      (node (ref "CMP14") (pin "2") (pinfunction "1_2") (pintype "input"))
      (node (ref "CMP2") (pin "P$4") (pinfunction "OUT_3_P$4") (pintype "output"))
      (node (ref "U$2") (pin "P$8") (pinfunction "D1_P$8") (pintype "input"))
    )
    (net (code "37") (name "OPCODE_IS_BRANCH_GROUP") (class "Default")
      (node (ref "CMP3") (pin "P$3") (pinfunction "2_P$3") (pintype "input"))
      (node (ref "CMP86") (pin "P$7") (pinfunction "OUT_6_P$7") (pintype "output"))
    )
    (net (code "38") (name "OPCODE_IS_DIV_STATE_0") (class "Default")
      (node (ref "CMP28") (pin "P$3") (pinfunction "B0_P$3") (pintype "input"))
      (node (ref "CMP90") (pin "P$2") (pinfunction "OUT_1_P$2") (pintype "output"))
    )
    (net (code "39") (name "OPCODE_IS_JMP_ABS") (class "Default")
      (node (ref "CMP14") (pin "3") (pinfunction "2_3") (pintype "input"))
      (node (ref "CMP2") (pin "P$5") (pinfunction "OUT_4_P$5") (pintype "output"))
      (node (ref "CMP3") (pin "P$2") (pinfunction "1_P$2") (pintype "input"))
      (node (ref "U$1") (pin "P$10") (pinfunction "E2_P$10") (pintype "input"))
    )
    (net (code "40") (name "OPCODE_IS_JMP_R0") (class "Default")
      (node (ref "CMP4") (pin "2") (pinfunction "1_2") (pintype "input"))
      (node (ref "CMP86") (pin "P$2") (pinfunction "OUT_1_P$2") (pintype "output"))
    )
    (net (code "41") (name "OPCODE_IS_JSR_ABS") (class "Default")
      (node (ref "CMP14") (pin "5") (pinfunction "4_5") (pintype "input"))
      (node (ref "CMP2") (pin "P$7") (pinfunction "OUT_6_P$7") (pintype "output"))
      (node (ref "CMP5") (pin "P$1") (pinfunction "A0_P$1") (pintype "input"))
    )
    (net (code "42") (name "OPCODE_IS_JSR_X_STATE_7") (class "Default")
      (node (ref "CMP2") (pin "P$15") (pinfunction "OUT_14_P$15") (pintype "output"))
      (node (ref "CMP23") (pin "6") (pinfunction "5_6") (pintype "input"))
    )
    (net (code "43") (name "OPCODE_IS_MOVER_SP") (class "Default")
      (node (ref "CMP4") (pin "5") (pinfunction "4_5") (pintype "input"))
      (node (ref "CMP86") (pin "P$5") (pinfunction "OUT_4_P$5") (pintype "output"))
    )
    (net (code "44") (name "OPCODE_IS_MUL") (class "Default")
      (node (ref "CMP31") (pin "P$4") (pinfunction "B1_P$4") (pintype "input"))
      (node (ref "CMP90") (pin "P$4") (pinfunction "OUT_3_P$4") (pintype "output"))
    )
    (net (code "45") (name "OPCODE_IS_RET") (class "Default")
      (node (ref "CMP21") (pin "P$1") (pinfunction "A2_P$1") (pintype "input"))
      (node (ref "CMP24") (pin "P$4") (pinfunction "B1_P$4") (pintype "input"))
      (node (ref "CMP86") (pin "P$11") (pinfunction "OUT_10_P$11") (pintype "output"))
    )
    (net (code "46") (name "OPCODE_IS_RETI") (class "Default")
      (node (ref "CMP21") (pin "P$2") (pinfunction "A1_P$2") (pintype "input"))
      (node (ref "CMP26") (pin "P$2") (pinfunction "2_P$2") (pintype "input"))
      (node (ref "CMP86") (pin "P$15") (pinfunction "OUT_14_P$15") (pintype "output"))
    )
    (net (code "47") (name "OPCODE_IS_SHIFT_XX") (class "Default")
      (node (ref "CMP14") (pin "1") (pinfunction "0_1") (pintype "input"))
      (node (ref "CMP2") (pin "P$3") (pinfunction "OUT_2_P$3") (pintype "output"))
      (node (ref "U$1") (pin "P$12") (pinfunction "F2_P$12") (pintype "input"))
    )
    (net (code "48") (name "OPCODE_IS_SQRT") (class "Default")
      (node (ref "CMP27") (pin "P$4") (pinfunction "B1_P$4") (pintype "input"))
      (node (ref "CMP90") (pin "P$1") (pinfunction "OUT_0_P$1") (pintype "output"))
    )
    (net (code "49") (name "OPCODE_IS_STACK_REL_GROUP") (class "Default")
      (node (ref "CMP2") (pin "P$9") (pinfunction "OUT_8_P$9") (pintype "output"))
      (node (ref "U$1") (pin "P$2") (pinfunction "A1_P$2") (pintype "input"))
    )
    (net (code "50") (name "OPCODE_IS_TRAP") (class "Default")
      (node (ref "CMP5") (pin "P$4") (pinfunction "B0_P$4") (pintype "input"))
      (node (ref "CMP90") (pin "P$5") (pinfunction "OUT_4_P$5") (pintype "output"))
    )
    (net (code "51") (name "RESET_FLAG") (class "Default")
      (node (ref "CMP4") (pin "1") (pinfunction "0_1") (pintype "input"))
      (node (ref "CMP6") (pin "IN") (pinfunction "IN_IN") (pintype "input"))
      (node (ref "CMP86") (pin "P$1") (pinfunction "OUT_0_P$1") (pintype "output"))
    )
    (net (code "52") (name "RESET_FLAG_N") (class "Default")
      (node (ref "CMP5") (pin "P$5") (pinfunction "B1_P$5") (pintype "input"))
      (node (ref "CMP6") (pin "N") (pinfunction "N_N") (pintype "output"))
    )
    (net (code "53") (name "RESET_IN") (class "Default")
      (node (ref "CMP8") (pin "IN") (pinfunction "IN_IN") (pintype "input"))
    )
    (net (code "54") (name "RESET_N") (class "Default")
      (node (ref "CMP39") (pin "EN0") (pinfunction "EN0_EN0") (pintype "input"))
      (node (ref "CMP8") (pin "N") (pinfunction "N_N") (pintype "output"))
    )
    (net (code "55") (name "RESET_VAL") (class "Default")
      (node (ref "CMP39") (pin "PORT1") (pinfunction "PORT1_PORT1") (pintype "input"))
      (node (ref "CMP7") (pin "INPUT") (pinfunction "OUT_INPUT") (pintype "output"))
    )
    (net (code "56") (name "SHIFT_IS_SHIFTING") (class "Default")
      (node (ref "CMP2") (pin "P$12") (pinfunction "OUT_11_P$12") (pintype "output"))
      (node (ref "U$1") (pin "P$13") (pinfunction "G1_P$13") (pintype "input"))
      (node (ref "U$1") (pin "P$14") (pinfunction "G2_P$14") (pintype "input"))
    )
    (net (code "57") (name "START_TRANSFER_CYCLE") (class "Default")
      (node (ref "CMP24") (pin "P$2") (pinfunction "A1_P$2") (pintype "input"))
      (node (ref "CMP25") (pin "P$3") (pinfunction "B0_P$3") (pintype "input"))
      (node (ref "CMP86") (pin "P$10") (pinfunction "OUT_9_P$10") (pintype "output"))
    )
    (net (code "58") (name "STATE_0") (class "Default")
      (node (ref "CMP13") (pin "P$1") (pinfunction "1_P$1") (pintype "input"))
      (node (ref "CMP24") (pin "P$3") (pinfunction "B0_P$3") (pintype "input"))
      (node (ref "CMP26") (pin "P$1") (pinfunction "1_P$1") (pintype "input"))
      (node (ref "CMP27") (pin "P$3") (pinfunction "B0_P$3") (pintype "input"))
      (node (ref "CMP31") (pin "P$3") (pinfunction "B0_P$3") (pintype "input"))
      (node (ref "CMP5") (pin "P$6") (pinfunction "B2_P$6") (pintype "input"))
      (node (ref "CMP9") (pin "P$1") (pinfunction "OUT_0_P$1") (pintype "output"))
      (node (ref "U$1") (pin "P$1") (pinfunction "A0_P$1") (pintype "input"))
      (node (ref "U$1") (pin "P$7") (pinfunction "D0_P$7") (pintype "input"))
      (node (ref "U$2") (pin "P$5") (pinfunction "C0_P$5") (pintype "input"))
    )
    (net (code "59") (name "STATE_1") (class "Default")
      (node (ref "CMP5") (pin "P$2") (pinfunction "A1_P$2") (pintype "input"))
      (node (ref "CMP5") (pin "P$3") (pinfunction "A2_P$3") (pintype "input"))
      (node (ref "CMP9") (pin "P$2") (pinfunction "OUT_1_P$2") (pintype "output"))
      (node (ref "U$1") (pin "P$11") (pinfunction "F1_P$11") (pintype "input"))
      (node (ref "U$1") (pin "P$9") (pinfunction "E1_P$9") (pintype "input"))
      (node (ref "U$2") (pin "P$7") (pinfunction "D0_P$7") (pintype "input"))
    )
    (net (code "60") (name "STATE_2") (class "Default")
      (node (ref "CMP9") (pin "P$3") (pinfunction "OUT_2_P$3") (pintype "output"))
      (node (ref "U$2") (pin "P$9") (pinfunction "E1_P$9") (pintype "input"))
    )
    (net (code "61") (name "STATE_3") (class "Default")
      (node (ref "CMP9") (pin "P$4") (pinfunction "OUT_3_P$4") (pintype "output"))
    )
    (net (code "62") (name "STATE_4") (class "Default")
      (node (ref "CMP25") (pin "P$1") (pinfunction "A0_P$1") (pintype "input"))
      (node (ref "CMP25") (pin "P$2") (pinfunction "A1_P$2") (pintype "input"))
      (node (ref "CMP9") (pin "P$5") (pinfunction "OUT_4_P$5") (pintype "output"))
    )
    (net (code "63") (name "STATE_5") (class "Default")
      (node (ref "CMP1") (pin "P$4") (pinfunction "B1_P$4") (pintype "input"))
      (node (ref "CMP9") (pin "P$6") (pinfunction "OUT_5_P$6") (pintype "output"))
      (node (ref "U$2") (pin "P$15") (pinfunction "H1_P$15") (pintype "input"))
    )
    (net (code "64") (name "STATE_6") (class "Default")
      (node (ref "CMP9") (pin "P$7") (pinfunction "OUT_6_P$7") (pintype "output"))
    )
    (net (code "65") (name "STATE_7") (class "Default")
      (node (ref "CMP1") (pin "P$2") (pinfunction "A1_P$2") (pintype "input"))
      (node (ref "CMP9") (pin "P$8") (pinfunction "OUT_7_P$8") (pintype "output"))
    )
    (net (code "66") (name "STATE_8") (class "Default")
      (node (ref "CMP24") (pin "P$5") (pinfunction "C0_P$5") (pintype "input"))
      (node (ref "CMP24") (pin "P$6") (pinfunction "C1_P$6") (pintype "input"))
      (node (ref "CMP9") (pin "P$9") (pinfunction "OUT_8_P$9") (pintype "output"))
    )
    (net (code "67") (name "STATE_9") (class "Default")
      (node (ref "CMP23") (pin "1") (pinfunction "0_1") (pintype "input"))
      (node (ref "CMP9") (pin "P$10") (pinfunction "OUT_9_P$10") (pintype "output"))
    )
    (net (code "68") (name "STATE_10") (class "Default")
      (node (ref "CMP27") (pin "P$2") (pinfunction "A1_P$2") (pintype "input"))
      (node (ref "CMP9") (pin "P$11") (pinfunction "OUT_10_P$11") (pintype "output"))
      (node (ref "U$2") (pin "P$2") (pinfunction "A1_P$2") (pintype "input"))
    )
    (net (code "69") (name "STATE_11") (class "Default")
      (node (ref "CMP28") (pin "P$2") (pinfunction "A1_P$2") (pintype "input"))
      (node (ref "CMP29") (pin "P$3") (pinfunction "3_P$3") (pintype "input"))
      (node (ref "CMP9") (pin "P$12") (pinfunction "OUT_11_P$12") (pintype "output"))
      (node (ref "U$2") (pin "P$11") (pinfunction "F1_P$11") (pintype "input"))
    )
    (net (code "70") (name "STATE_12") (class "Default")
      (node (ref "CMP23") (pin "2") (pinfunction "1_2") (pintype "input"))
      (node (ref "CMP9") (pin "P$13") (pinfunction "OUT_12_P$13") (pintype "output"))
    )
    (net (code "71") (name "STATE_13") (class "Default")
      (node (ref "CMP30") (pin "P$3") (pinfunction "3_P$3") (pintype "input"))
      (node (ref "CMP31") (pin "P$2") (pinfunction "A1_P$2") (pintype "input"))
      (node (ref "CMP9") (pin "P$14") (pinfunction "OUT_13_P$14") (pintype "output"))
      (node (ref "U$2") (pin "P$3") (pinfunction "B0_P$3") (pintype "input"))
    )
    (net (code "72") (name "STATE_14") (class "Default")
      (node (ref "CMP23") (pin "3") (pinfunction "2_3") (pintype "input"))
      (node (ref "CMP9") (pin "P$15") (pinfunction "OUT_14_P$15") (pintype "output"))
    )
    (net (code "73") (name "STATE_15") (class "Default")
      (node (ref "CMP9") (pin "P$16") (pinfunction "OUT_15_P$16") (pintype "output"))
    )
    (net (code "74") (name "TRAP_STATE_7") (class "Default")
      (node (ref "CMP10") (pin "P$10") (pinfunction "IN_9_P$10") (pintype "input"))
      (node (ref "CMP86") (pin "P$16") (pinfunction "OUT_15_P$16") (pintype "output"))
    )
    (net (code "75") (name "TYPE_BIT_IS_SIGNED") (class "Default")
      (node (ref "CMP29") (pin "P$2") (pinfunction "2_P$2") (pintype "input"))
      (node (ref "CMP30") (pin "P$1") (pinfunction "1_P$1") (pintype "input"))
      (node (ref "CMP90") (pin "P$3") (pinfunction "OUT_2_P$3") (pintype "output"))
    )
    (net (code "76") (name "UNSIGNED_15") (class "Default")
      (node (ref "CMP86") (pin "P$8") (pinfunction "OUT_7_P$8") (pintype "output"))
      (node (ref "U$2") (pin "P$12") (pinfunction "F2_P$12") (pintype "input"))
      (node (ref "U$2") (pin "P$4") (pinfunction "B1_P$4") (pintype "input"))
    )
    (net (code "77") (name "WILL_BE_1__LDI") (class "Default")
      (node (ref "CMP14") (pin "6") (pinfunction "5_6") (pintype "input"))
      (node (ref "CMP2") (pin "P$8") (pinfunction "OUT_7_P$8") (pintype "output"))
    )
    (net (code "78") (name "WILL_BE_1__OPTIONS") (class "Default")
      (node (ref "CMP13") (pin "P$2") (pinfunction "2_P$2") (pintype "input"))
      (node (ref "CMP14") (pin "OUT_P") (pinfunction "P_OUT_P") (pintype "output"))
    )
    (net (code "79") (name "WILL_BE_3__FROM_0") (class "Default")
      (node (ref "CMP4") (pin "OUT_P") (pinfunction "P_OUT_P") (pintype "output"))
      (node (ref "U$2") (pin "P$6") (pinfunction "C1_P$6") (pintype "input"))
    )
    (net (code "80") (name "WILL_BE_3__FROM_2") (class "Default")
      (node (ref "CMP3") (pin "OUT_P") (pinfunction "P_OUT_P") (pintype "output"))
      (node (ref "U$2") (pin "P$10") (pinfunction "E2_P$10") (pintype "input"))
    )
    (net (code "81") (name "WILL_BE_3__FROM_5") (class "Default")
      (node (ref "CMP21") (pin "OUT_P") (pinfunction "P_OUT_P") (pintype "output"))
      (node (ref "U$2") (pin "P$16") (pinfunction "H2_P$16") (pintype "input"))
    )
    (net (code "82") (name "WILL_BE_3__FROM_MANY") (class "Default")
      (node (ref "CMP23") (pin "7") (pinfunction "6_7") (pintype "input"))
      (node (ref "U$2") (pin "OUT_P") (pinfunction "P_OUT_P") (pintype "output"))
    )
    (net (code "83") (name "WILL_BE_STATE_0") (class "Default")
      (node (ref "CMP10") (pin "P$1") (pinfunction "IN_0_P$1") (pintype "input"))
      (node (ref "CMP11") (pin "OUT_P") (pinfunction "P_OUT_P") (pintype "output"))
    )
    (net (code "84") (name "WILL_BE_STATE_1") (class "Default")
      (node (ref "CMP10") (pin "P$2") (pinfunction "IN_1_P$2") (pintype "input"))
      (node (ref "CMP13") (pin "OUT_P") (pinfunction "P_OUT_P") (pintype "output"))
    )
    (net (code "85") (name "WILL_BE_STATE_2") (class "Default")
      (node (ref "CMP10") (pin "P$3") (pinfunction "IN_2_P$3") (pintype "input"))
      (node (ref "U$1") (pin "OUT_P") (pinfunction "P_OUT_P") (pintype "output"))
    )
    (net (code "86") (name "WILL_BE_STATE_3") (class "Default")
      (node (ref "CMP10") (pin "P$4") (pinfunction "IN_3_P$4") (pintype "input"))
      (node (ref "CMP23") (pin "OUT_P") (pinfunction "P_OUT_P") (pintype "output"))
    )
    (net (code "87") (name "WILL_BE_STATE_4") (class "Default")
      (node (ref "CMP10") (pin "P$5") (pinfunction "IN_4_P$5") (pintype "input"))
      (node (ref "CMP24") (pin "OUT_P") (pinfunction "P_OUT_P") (pintype "output"))
    )
    (net (code "88") (name "WILL_BE_STATE_5") (class "Default")
      (node (ref "CMP10") (pin "P$6") (pinfunction "IN_5_P$6") (pintype "input"))
      (node (ref "CMP25") (pin "OUT_P") (pinfunction "P_OUT_P") (pintype "output"))
    )
    (net (code "89") (name "WILL_BE_STATE_6") (class "Default")
      (node (ref "CMP10") (pin "P$7") (pinfunction "IN_6_P$7") (pintype "input"))
      (node (ref "CMP86") (pin "P$13") (pinfunction "OUT_12_P$13") (pintype "output"))
    )
    (net (code "90") (name "WILL_BE_STATE_7") (class "Default")
      (node (ref "CMP10") (pin "P$8") (pinfunction "IN_7_P$8") (pintype "input"))
      (node (ref "CMP86") (pin "P$14") (pinfunction "OUT_13_P$14") (pintype "output"))
    )
    (net (code "91") (name "WILL_BE_STATE_8") (class "Default")
      (node (ref "CMP10") (pin "P$9") (pinfunction "IN_8_P$9") (pintype "input"))
      (node (ref "CMP26") (pin "OUT_P") (pinfunction "P_OUT_P") (pintype "output"))
    )
    (net (code "92") (name "WILL_BE_STATE_10") (class "Default")
      (node (ref "CMP10") (pin "P$11") (pinfunction "IN_10_P$11") (pintype "input"))
      (node (ref "CMP27") (pin "OUT_P") (pinfunction "P_OUT_P") (pintype "output"))
    )
    (net (code "93") (name "WILL_BE_STATE_11") (class "Default")
      (node (ref "CMP10") (pin "P$12") (pinfunction "IN_11_P$12") (pintype "input"))
      (node (ref "CMP28") (pin "OUT_P") (pinfunction "P_OUT_P") (pintype "output"))
    )
    (net (code "94") (name "WILL_BE_STATE_12") (class "Default")
      (node (ref "CMP10") (pin "P$13") (pinfunction "IN_12_P$13") (pintype "input"))
      (node (ref "CMP29") (pin "OUT_P") (pinfunction "P_OUT_P") (pintype "output"))
    )
    (net (code "95") (name "WILL_BE_STATE_13") (class "Default")
      (node (ref "CMP10") (pin "P$14") (pinfunction "IN_13_P$14") (pintype "input"))
      (node (ref "CMP31") (pin "OUT_P") (pinfunction "P_OUT_P") (pintype "output"))
    )
    (net (code "96") (name "WILL_BE_STATE_14") (class "Default")
      (node (ref "CMP10") (pin "P$15") (pinfunction "IN_14_P$15") (pintype "input"))
      (node (ref "CMP30") (pin "OUT_P") (pinfunction "P_OUT_P") (pintype "output"))
    )
    (net (code "97") (name "WILL_BE_STATE_15") (class "Default")
      (node (ref "CMP10") (pin "P$16") (pinfunction "IN_15_P$16") (pintype "input"))
      (node (ref "CMP5") (pin "OUT_P") (pinfunction "P_OUT_P") (pintype "output"))
    )
    (net (code "98") (name "unconnected-(CMP1-N-PadOUT_M)") (class "Default")
      (node (ref "CMP1") (pin "OUT_M") (pinfunction "N_OUT_M") (pintype "output"))
    )
    (net (code "99") (name "unconnected-(CMP3-N-PadOUT_M)") (class "Default")
      (node (ref "CMP3") (pin "OUT_M") (pinfunction "N_OUT_M") (pintype "output"))
    )
    (net (code "100") (name "unconnected-(CMP4-N-PadOUT_M)") (class "Default")
      (node (ref "CMP4") (pin "OUT_M") (pinfunction "N_OUT_M") (pintype "output"))
    )
    (net (code "101") (name "unconnected-(CMP5-N-PadOUT_M)") (class "Default")
      (node (ref "CMP5") (pin "OUT_M") (pinfunction "N_OUT_M") (pintype "output"))
    )
    (net (code "102") (name "unconnected-(CMP6-PadP)") (class "Default")
      (node (ref "CMP6") (pin "P") (pinfunction "P_P") (pintype "output"))
    )
    (net (code "103") (name "unconnected-(CMP7-IN_0-PadP$1)") (class "Default")
      (node (ref "CMP7") (pin "P$1") (pinfunction "IN_0_P$1") (pintype "input"))
    )
    (net (code "104") (name "unconnected-(CMP11-N-PadOUT_M)") (class "Default")
      (node (ref "CMP11") (pin "OUT_M") (pinfunction "N_OUT_M") (pintype "output"))
    )
    (net (code "105") (name "unconnected-(CMP13-N-PadOUT_M)") (class "Default")
      (node (ref "CMP13") (pin "OUT_M") (pinfunction "N_OUT_M") (pintype "output"))
    )
    (net (code "106") (name "unconnected-(CMP14-N-PadOUT_M)") (class "Default")
      (node (ref "CMP14") (pin "OUT_M") (pinfunction "N_OUT_M") (pintype "output"))
    )
    (net (code "107") (name "unconnected-(CMP21-N-PadOUT_M)") (class "Default")
      (node (ref "CMP21") (pin "OUT_M") (pinfunction "N_OUT_M") (pintype "output"))
    )
    (net (code "108") (name "unconnected-(CMP23-N-PadOUT_M)") (class "Default")
      (node (ref "CMP23") (pin "OUT_M") (pinfunction "N_OUT_M") (pintype "output"))
    )
    (net (code "109") (name "unconnected-(CMP24-N-PadOUT_M)") (class "Default")
      (node (ref "CMP24") (pin "OUT_M") (pinfunction "N_OUT_M") (pintype "output"))
    )
    (net (code "110") (name "unconnected-(CMP25-N-PadOUT_M)") (class "Default")
      (node (ref "CMP25") (pin "OUT_M") (pinfunction "N_OUT_M") (pintype "output"))
    )
    (net (code "111") (name "unconnected-(CMP26-N-PadOUT_M)") (class "Default")
      (node (ref "CMP26") (pin "OUT_M") (pinfunction "N_OUT_M") (pintype "output"))
    )
    (net (code "112") (name "unconnected-(CMP27-N-PadOUT_M)") (class "Default")
      (node (ref "CMP27") (pin "OUT_M") (pinfunction "N_OUT_M") (pintype "output"))
    )
    (net (code "113") (name "unconnected-(CMP28-N-PadOUT_M)") (class "Default")
      (node (ref "CMP28") (pin "OUT_M") (pinfunction "N_OUT_M") (pintype "output"))
    )
    (net (code "114") (name "unconnected-(CMP29-M-PadOUT_M)") (class "Default")
      (node (ref "CMP29") (pin "OUT_M") (pinfunction "M_OUT_M") (pintype "output"))
    )
    (net (code "115") (name "unconnected-(CMP30-M-PadOUT_M)") (class "Default")
      (node (ref "CMP30") (pin "OUT_M") (pinfunction "M_OUT_M") (pintype "output"))
    )
    (net (code "116") (name "unconnected-(CMP31-N-PadOUT_M)") (class "Default")
      (node (ref "CMP31") (pin "OUT_M") (pinfunction "N_OUT_M") (pintype "output"))
    )
    (net (code "117") (name "unconnected-(CMP46-PadP)") (class "Default")
      (node (ref "CMP46") (pin "P") (pinfunction "P_P") (pintype "output"))
    )
    (net (code "118") (name "unconnected-(CMP90-OUT_5-PadP$6)") (class "Default")
      (node (ref "CMP90") (pin "P$6") (pinfunction "OUT_5_P$6") (pintype "output"))
    )
    (net (code "119") (name "unconnected-(CMP90-OUT_6-PadP$7)") (class "Default")
      (node (ref "CMP90") (pin "P$7") (pinfunction "OUT_6_P$7") (pintype "output"))
    )
    (net (code "120") (name "unconnected-(CMP90-OUT_7-PadP$8)") (class "Default")
      (node (ref "CMP90") (pin "P$8") (pinfunction "OUT_7_P$8") (pintype "output"))
    )
    (net (code "121") (name "unconnected-(CMP90-OUT_8-PadP$9)") (class "Default")
      (node (ref "CMP90") (pin "P$9") (pinfunction "OUT_8_P$9") (pintype "output"))
    )
    (net (code "122") (name "unconnected-(CMP90-OUT_9-PadP$10)") (class "Default")
      (node (ref "CMP90") (pin "P$10") (pinfunction "OUT_9_P$10") (pintype "output"))
    )
    (net (code "123") (name "unconnected-(CMP90-OUT_10-PadP$11)") (class "Default")
      (node (ref "CMP90") (pin "P$11") (pinfunction "OUT_10_P$11") (pintype "output"))
    )
    (net (code "124") (name "unconnected-(CMP90-OUT_11-PadP$12)") (class "Default")
      (node (ref "CMP90") (pin "P$12") (pinfunction "OUT_11_P$12") (pintype "output"))
    )
    (net (code "125") (name "unconnected-(CMP90-OUT_12-PadP$13)") (class "Default")
      (node (ref "CMP90") (pin "P$13") (pinfunction "OUT_12_P$13") (pintype "output"))
    )
    (net (code "126") (name "unconnected-(CMP90-OUT_13-PadP$14)") (class "Default")
      (node (ref "CMP90") (pin "P$14") (pinfunction "OUT_13_P$14") (pintype "output"))
    )
    (net (code "127") (name "unconnected-(CMP90-OUT_14-PadP$15)") (class "Default")
      (node (ref "CMP90") (pin "P$15") (pinfunction "OUT_14_P$15") (pintype "output"))
    )
    (net (code "128") (name "unconnected-(CMP90-OUT_15-PadP$16)") (class "Default")
      (node (ref "CMP90") (pin "P$16") (pinfunction "OUT_15_P$16") (pintype "output"))
    )
    (net (code "129") (name "unconnected-(U$1-N-PadOUT_M)") (class "Default")
      (node (ref "U$1") (pin "OUT_M") (pinfunction "N_OUT_M") (pintype "output"))
    )
    (net (code "130") (name "unconnected-(U$2-N-PadOUT_M)") (class "Default")
      (node (ref "U$2") (pin "OUT_M") (pinfunction "N_OUT_M") (pintype "output"))
    )
  )
)
